# hub-carrier-p4.net
KiCad netlist of a schematic drawn in EAGLE
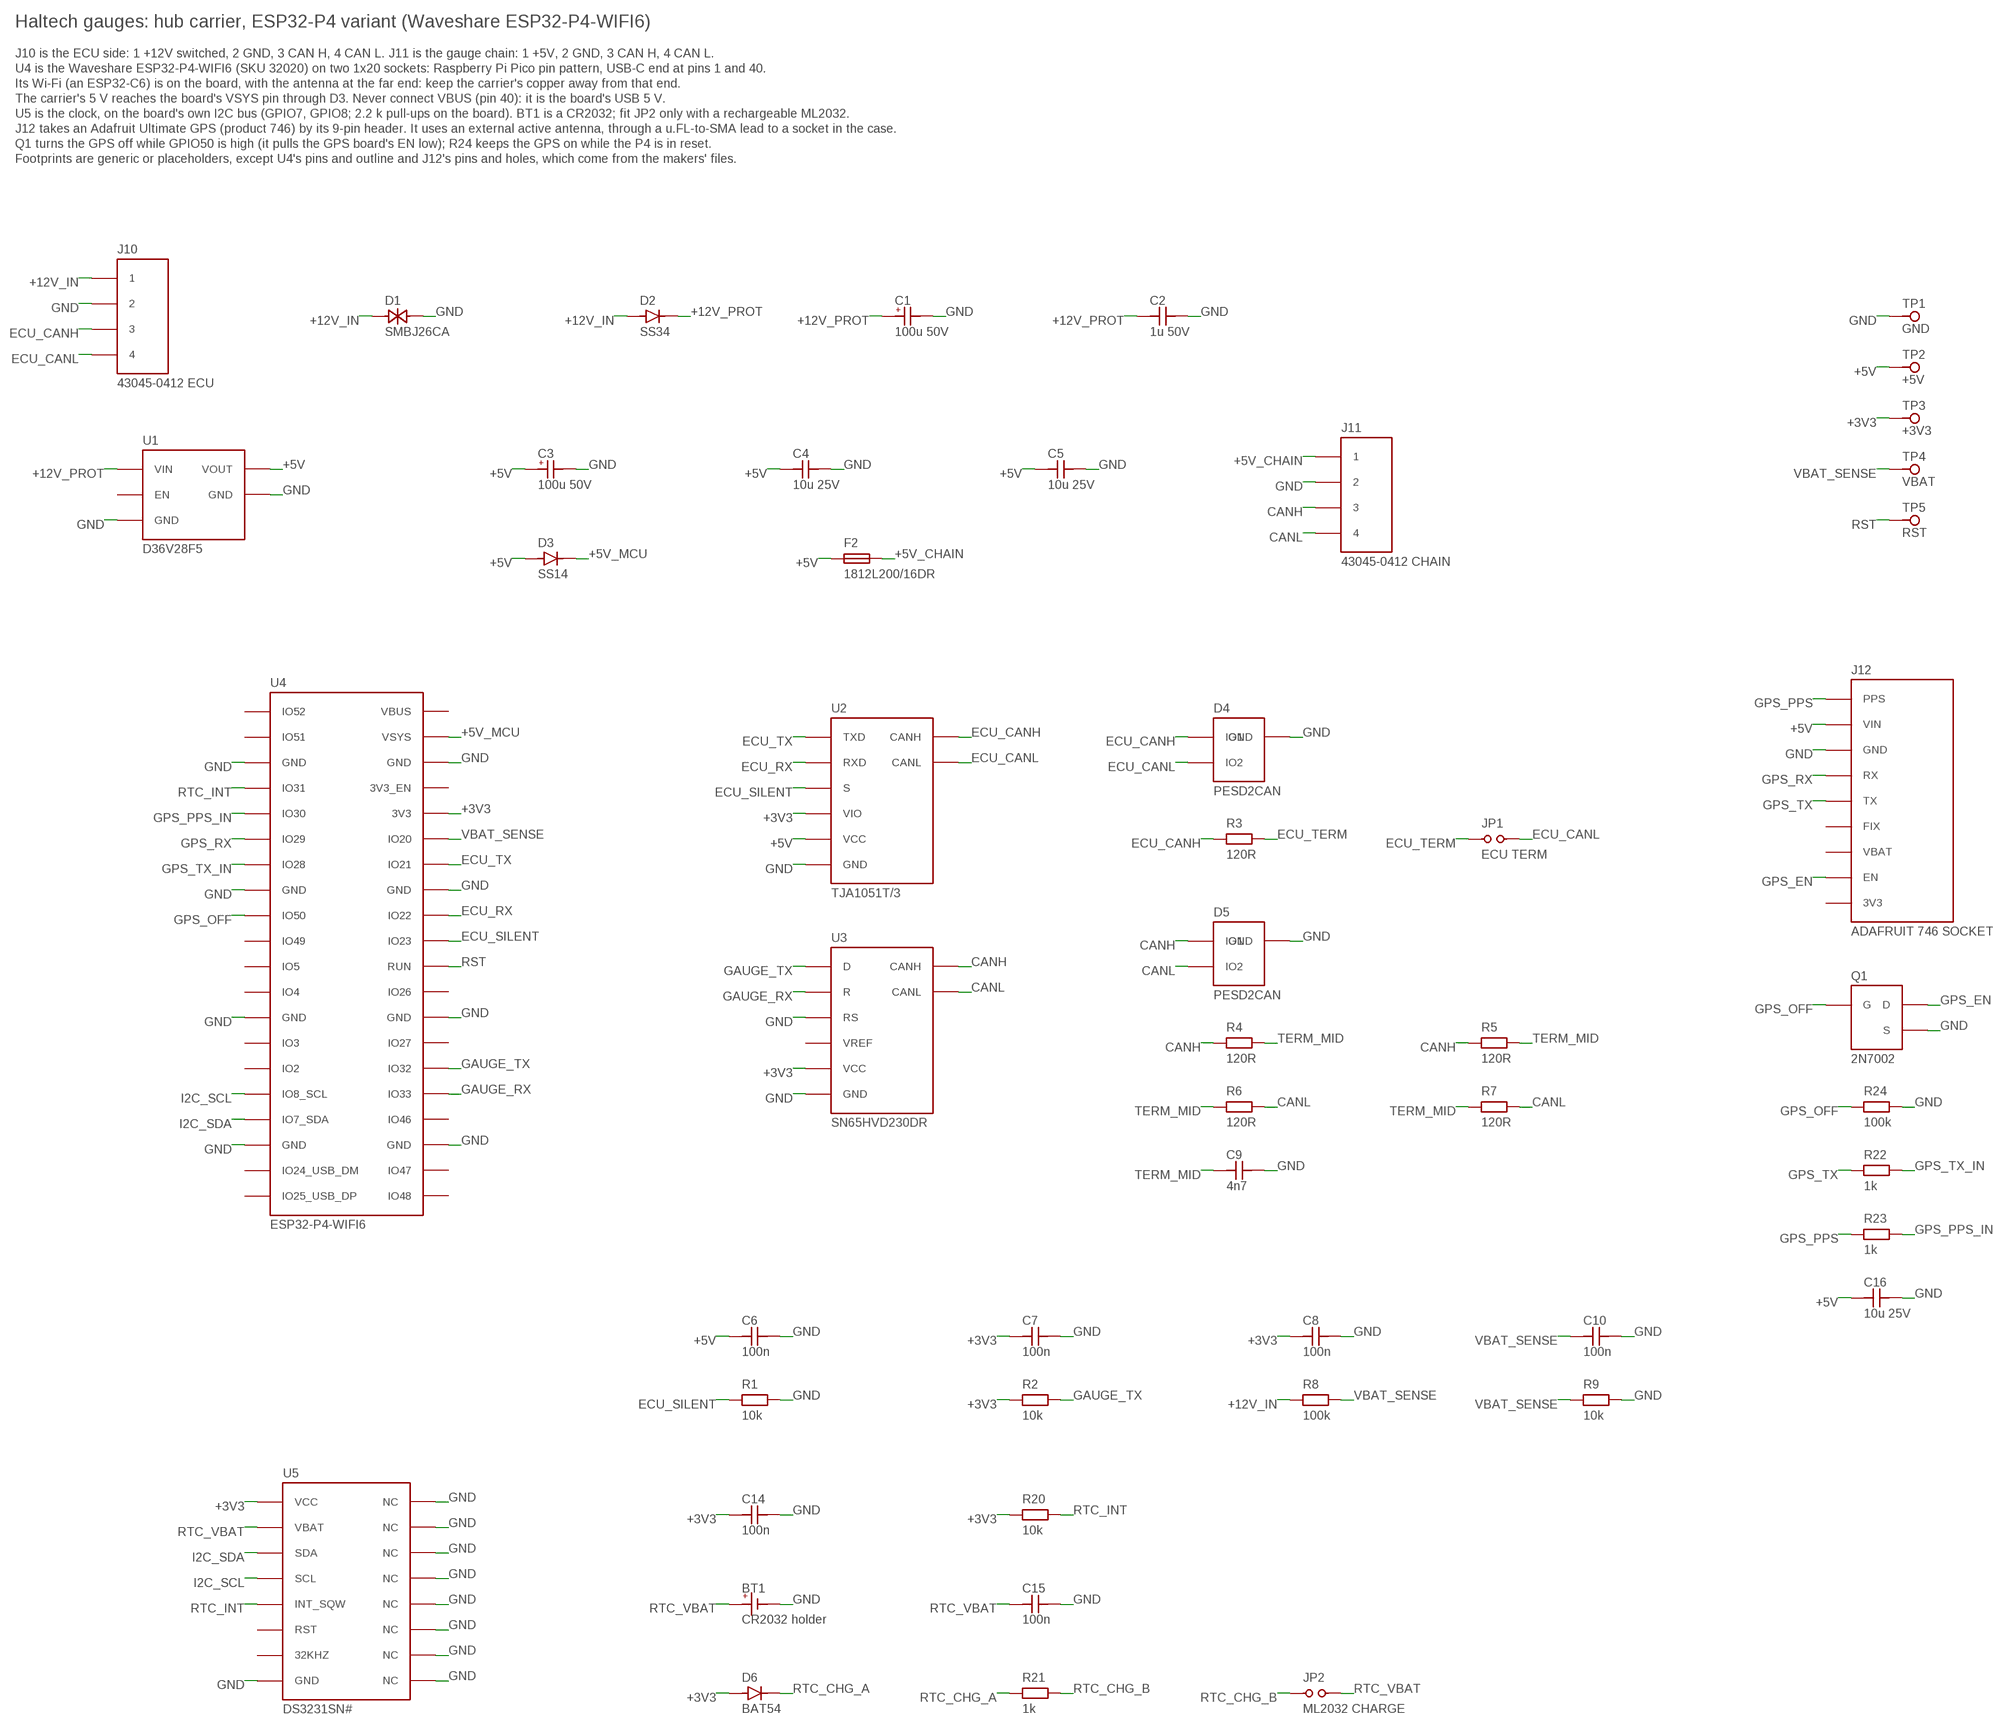
[diagram p0: schematic, sheet 1]

(export (version "E")
  (design (tool "Eeschema 10.0.6"))
  (components
    (comp (ref "BT1")
      (value "CR2032 holder")
      (footprint "eagle-import:CR2032-HOLDER-PLACEHOLDER")
      (libsource (lib "eagle-import") (part "BATTERY-2032"))
    )
    (comp (ref "C1")
      (value "100u 50V")
      (footprint "eagle-import:CAP-SMD-8X10")
      (fields (field (name "LCSC") "C116241"))
      (libsource (lib "eagle-import") (part "CPOL-8X10"))
    )
    (comp (ref "C2")
      (value "1u 50V")
      (footprint "eagle-import:0805")
      (fields (field (name "LCSC") "C28323"))
      (libsource (lib "eagle-import") (part "C0805"))
    )
    (comp (ref "C3")
      (value "100u 50V")
      (footprint "eagle-import:CAP-SMD-8X10")
      (fields (field (name "LCSC") "C116241"))
      (libsource (lib "eagle-import") (part "CPOL-8X10"))
    )
    (comp (ref "C4")
      (value "10u 25V")
      (footprint "eagle-import:0805")
      (fields (field (name "LCSC") "C15850"))
      (libsource (lib "eagle-import") (part "C0805"))
    )
    (comp (ref "C5")
      (value "10u 25V")
      (footprint "eagle-import:0805")
      (fields (field (name "LCSC") "C15850"))
      (libsource (lib "eagle-import") (part "C0805"))
    )
    (comp (ref "C6")
      (value "100n")
      (footprint "eagle-import:0805")
      (fields (field (name "LCSC") "C49678"))
      (libsource (lib "eagle-import") (part "C0805"))
    )
    (comp (ref "C7")
      (value "100n")
      (footprint "eagle-import:0805")
      (fields (field (name "LCSC") "C49678"))
      (libsource (lib "eagle-import") (part "C0805"))
    )
    (comp (ref "C8")
      (value "100n")
      (footprint "eagle-import:0805")
      (fields (field (name "LCSC") "C49678"))
      (libsource (lib "eagle-import") (part "C0805"))
    )
    (comp (ref "C9")
      (value "4n7")
      (footprint "eagle-import:0805")
      (fields (field (name "LCSC") "C1744"))
      (libsource (lib "eagle-import") (part "C0805"))
    )
    (comp (ref "C10")
      (value "100n")
      (footprint "eagle-import:0805")
      (fields (field (name "LCSC") "C49678"))
      (libsource (lib "eagle-import") (part "C0805"))
    )
    (comp (ref "C14")
      (value "100n")
      (footprint "eagle-import:0805")
      (fields (field (name "LCSC") "C49678"))
      (libsource (lib "eagle-import") (part "C0805"))
    )
    (comp (ref "C15")
      (value "100n")
      (footprint "eagle-import:0805")
      (fields (field (name "LCSC") "C49678"))
      (libsource (lib "eagle-import") (part "C0805"))
    )
    (comp (ref "C16")
      (value "10u 25V")
      (footprint "eagle-import:0805")
      (fields (field (name "LCSC") "C15850"))
      (libsource (lib "eagle-import") (part "C0805"))
    )
    (comp (ref "D1")
      (value "SMBJ26CA")
      (footprint "eagle-import:SMB")
      (fields (field (name "LCSC") "C515606"))
      (libsource (lib "eagle-import") (part "TVS-SMB"))
    )
    (comp (ref "D2")
      (value "SS34")
      (footprint "eagle-import:SMA")
      (fields (field (name "LCSC") "C8678"))
      (libsource (lib "eagle-import") (part "SCHOTTKY-SMA"))
    )
    (comp (ref "D3")
      (value "SS14")
      (footprint "eagle-import:SMA")
      (fields (field (name "LCSC") "C2480"))
      (libsource (lib "eagle-import") (part "SCHOTTKY-SMA"))
    )
    (comp (ref "D4")
      (value "PESD2CAN")
      (footprint "eagle-import:SOT23")
      (fields (field (name "LCSC") "C75176"))
      (libsource (lib "eagle-import") (part "PESD2CAN"))
    )
    (comp (ref "D5")
      (value "PESD2CAN")
      (footprint "eagle-import:SOT23")
      (fields (field (name "LCSC") "C75176"))
      (libsource (lib "eagle-import") (part "PESD2CAN"))
    )
    (comp (ref "D6")
      (value "BAT54")
      (footprint "eagle-import:SOT23")
      (fields (field (name "LCSC") "C8590"))
      (libsource (lib "eagle-import") (part "BAT54"))
    )
    (comp (ref "F2")
      (value "1812L200/16DR")
      (footprint "eagle-import:1812")
      (fields (field (name "LCSC") "C439873"))
      (libsource (lib "eagle-import") (part "POLYFUSE-1812"))
    )
    (comp (ref "J10")
      (value "43045-0412 ECU")
      (footprint "eagle-import:MOLEX-43045-0412")
      (libsource (lib "eagle-import") (part "MICROFIT-2X2"))
    )
    (comp (ref "J11")
      (value "43045-0412 CHAIN")
      (footprint "eagle-import:MOLEX-43045-0412")
      (libsource (lib "eagle-import") (part "MICROFIT-2X2"))
    )
    (comp (ref "J12")
      (value "ADAFRUIT 746 SOCKET")
      (footprint "eagle-import:ADAFRUIT-ULTIMATE-GPS")
      (libsource (lib "eagle-import") (part "ADAFRUIT-ULTIMATE-GPS"))
    )
    (comp (ref "JP1")
      (value "ECU TERM")
      (footprint "eagle-import:HDR-1X2")
      (libsource (lib "eagle-import") (part "JUMPER-2"))
    )
    (comp (ref "JP2")
      (value "ML2032 CHARGE")
      (footprint "eagle-import:HDR-1X2")
      (libsource (lib "eagle-import") (part "JUMPER-2"))
    )
    (comp (ref "Q1")
      (value "2N7002")
      (footprint "eagle-import:SOT23")
      (fields (field (name "LCSC") "C8545"))
      (libsource (lib "eagle-import") (part "2N7002"))
    )
    (comp (ref "R1")
      (value "10k")
      (footprint "eagle-import:0805")
      (fields (field (name "LCSC") "C17414"))
      (libsource (lib "eagle-import") (part "R0805"))
    )
    (comp (ref "R2")
      (value "10k")
      (footprint "eagle-import:0805")
      (fields (field (name "LCSC") "C17414"))
      (libsource (lib "eagle-import") (part "R0805"))
    )
    (comp (ref "R3")
      (value "120R")
      (footprint "eagle-import:1206")
      (fields (field (name "LCSC") "C17909"))
      (libsource (lib "eagle-import") (part "R1206"))
    )
    (comp (ref "R4")
      (value "120R")
      (footprint "eagle-import:1206")
      (fields (field (name "LCSC") "C17909"))
      (libsource (lib "eagle-import") (part "R1206"))
    )
    (comp (ref "R5")
      (value "120R")
      (footprint "eagle-import:1206")
      (fields (field (name "LCSC") "C17909"))
      (libsource (lib "eagle-import") (part "R1206"))
    )
    (comp (ref "R6")
      (value "120R")
      (footprint "eagle-import:1206")
      (fields (field (name "LCSC") "C17909"))
      (libsource (lib "eagle-import") (part "R1206"))
    )
    (comp (ref "R7")
      (value "120R")
      (footprint "eagle-import:1206")
      (fields (field (name "LCSC") "C17909"))
      (libsource (lib "eagle-import") (part "R1206"))
    )
    (comp (ref "R8")
      (value "100k")
      (footprint "eagle-import:0805")
      (fields (field (name "LCSC") "C149504"))
      (libsource (lib "eagle-import") (part "R0805"))
    )
    (comp (ref "R9")
      (value "10k")
      (footprint "eagle-import:0805")
      (fields (field (name "LCSC") "C17414"))
      (libsource (lib "eagle-import") (part "R0805"))
    )
    (comp (ref "R20")
      (value "10k")
      (footprint "eagle-import:0805")
      (fields (field (name "LCSC") "C17414"))
      (libsource (lib "eagle-import") (part "R0805"))
    )
    (comp (ref "R21")
      (value "1k")
      (footprint "eagle-import:0805")
      (fields (field (name "LCSC") "C17513"))
      (libsource (lib "eagle-import") (part "R0805"))
    )
    (comp (ref "R22")
      (value "1k")
      (footprint "eagle-import:0805")
      (fields (field (name "LCSC") "C17513"))
      (libsource (lib "eagle-import") (part "R0805"))
    )
    (comp (ref "R23")
      (value "1k")
      (footprint "eagle-import:0805")
      (fields (field (name "LCSC") "C17513"))
      (libsource (lib "eagle-import") (part "R0805"))
    )
    (comp (ref "R24")
      (value "100k")
      (footprint "eagle-import:0805")
      (fields (field (name "LCSC") "C149504"))
      (libsource (lib "eagle-import") (part "R0805"))
    )
    (comp (ref "TP1")
      (value "GND")
      (footprint "eagle-import:TESTPAD")
      (libsource (lib "eagle-import") (part "TESTPOINT"))
    )
    (comp (ref "TP2")
      (value "+5V")
      (footprint "eagle-import:TESTPAD")
      (libsource (lib "eagle-import") (part "TESTPOINT"))
    )
    (comp (ref "TP3")
      (value "+3V3")
      (footprint "eagle-import:TESTPAD")
      (libsource (lib "eagle-import") (part "TESTPOINT"))
    )
    (comp (ref "TP4")
      (value "VBAT")
      (footprint "eagle-import:TESTPAD")
      (libsource (lib "eagle-import") (part "TESTPOINT"))
    )
    (comp (ref "TP5")
      (value "RST")
      (footprint "eagle-import:TESTPAD")
      (libsource (lib "eagle-import") (part "TESTPOINT"))
    )
    (comp (ref "U1")
      (value "D36V28F5")
      (footprint "eagle-import:POLOLU-D36V28F-PLACEHOLDER")
      (libsource (lib "eagle-import") (part "POLOLU-D36V28F5"))
    )
    (comp (ref "U2")
      (value "TJA1051T/3")
      (footprint "eagle-import:SOIC8")
      (fields (field (name "LCSC") "C38695"))
      (libsource (lib "eagle-import") (part "TJA1051T-3"))
    )
    (comp (ref "U3")
      (value "SN65HVD230DR")
      (footprint "eagle-import:SOIC8")
      (fields (field (name "LCSC") "C12084"))
      (libsource (lib "eagle-import") (part "SN65HVD230"))
    )
    (comp (ref "U4")
      (value "ESP32-P4-WIFI6")
      (footprint "eagle-import:WAVESHARE-ESP32-P4-WIFI6")
      (libsource (lib "eagle-import") (part "WAVESHARE-ESP32-P4-WIFI6"))
    )
    (comp (ref "U5")
      (value "DS3231SN#")
      (footprint "eagle-import:SOIC16W")
      (fields (field (name "LCSC") "C9866"))
      (libsource (lib "eagle-import") (part "DS3231SN"))
    )
  )
  (nets
    (net (code "1") (name "/+3V3") (class "Default")
      (node (ref "C14") (pin "1") (pinfunction "1_1") (pintype "passive"))
      (node (ref "C7") (pin "1") (pinfunction "1_1") (pintype "passive"))
      (node (ref "C8") (pin "1") (pinfunction "1_1") (pintype "passive"))
      (node (ref "D6") (pin "1") (pinfunction "A_1") (pintype "passive"))
      (node (ref "R2") (pin "1") (pinfunction "1_1") (pintype "passive"))
      (node (ref "R20") (pin "1") (pinfunction "1_1") (pintype "passive"))
      (node (ref "TP3") (pin "1") (pinfunction "TP_1") (pintype "passive"))
      (node (ref "U2") (pin "5") (pinfunction "VIO_5") (pintype "passive"))
      (node (ref "U3") (pin "3") (pinfunction "VCC_3") (pintype "passive"))
      (node (ref "U4") (pin "36") (pinfunction "3V3_36") (pintype "passive"))
      (node (ref "U5") (pin "2") (pinfunction "VCC_2") (pintype "passive"))
    )
    (net (code "2") (name "/+5V") (class "Default")
      (node (ref "C16") (pin "1") (pinfunction "1_1") (pintype "passive"))
      (node (ref "C3") (pin "1") (pinfunction "+_1") (pintype "passive"))
      (node (ref "C4") (pin "1") (pinfunction "1_1") (pintype "passive"))
      (node (ref "C5") (pin "1") (pinfunction "1_1") (pintype "passive"))
      (node (ref "C6") (pin "1") (pinfunction "1_1") (pintype "passive"))
      (node (ref "D3") (pin "2") (pinfunction "A_2") (pintype "passive"))
      (node (ref "F2") (pin "1") (pinfunction "1_1") (pintype "passive"))
      (node (ref "J12") (pin "2") (pinfunction "VIN_2") (pintype "passive"))
      (node (ref "TP2") (pin "1") (pinfunction "TP_1") (pintype "passive"))
      (node (ref "U1") (pin "VOUT") (pinfunction "VOUT_VOUT") (pintype "passive"))
      (node (ref "U2") (pin "3") (pinfunction "VCC_3") (pintype "passive"))
    )
    (net (code "3") (name "/+5V_CHAIN") (class "Default")
      (node (ref "F2") (pin "2") (pinfunction "2_2") (pintype "passive"))
      (node (ref "J11") (pin "1") (pinfunction "1_1") (pintype "passive"))
    )
    (net (code "4") (name "/+5V_MCU") (class "Default")
      (node (ref "D3") (pin "1") (pinfunction "K_1") (pintype "passive"))
      (node (ref "U4") (pin "39") (pinfunction "VSYS_39") (pintype "passive"))
    )
    (net (code "5") (name "/+12V_IN") (class "Default")
      (node (ref "D1") (pin "1") (pinfunction "1_1") (pintype "passive"))
      (node (ref "D2") (pin "2") (pinfunction "A_2") (pintype "passive"))
      (node (ref "J10") (pin "1") (pinfunction "1_1") (pintype "passive"))
      (node (ref "R8") (pin "1") (pinfunction "1_1") (pintype "passive"))
    )
    (net (code "6") (name "/+12V_PROT") (class "Default")
      (node (ref "C1") (pin "1") (pinfunction "+_1") (pintype "passive"))
      (node (ref "C2") (pin "1") (pinfunction "1_1") (pintype "passive"))
      (node (ref "D2") (pin "1") (pinfunction "K_1") (pintype "passive"))
      (node (ref "U1") (pin "VIN") (pinfunction "VIN_VIN") (pintype "passive"))
    )
    (net (code "7") (name "/CANH") (class "Default")
      (node (ref "D5") (pin "1") (pinfunction "IO1_1") (pintype "passive"))
      (node (ref "J11") (pin "3") (pinfunction "3_3") (pintype "passive"))
      (node (ref "R4") (pin "1") (pinfunction "1_1") (pintype "passive"))
      (node (ref "R5") (pin "1") (pinfunction "1_1") (pintype "passive"))
      (node (ref "U3") (pin "7") (pinfunction "CANH_7") (pintype "passive"))
    )
    (net (code "8") (name "/CANL") (class "Default")
      (node (ref "D5") (pin "2") (pinfunction "IO2_2") (pintype "passive"))
      (node (ref "J11") (pin "4") (pinfunction "4_4") (pintype "passive"))
      (node (ref "R6") (pin "2") (pinfunction "2_2") (pintype "passive"))
      (node (ref "R7") (pin "2") (pinfunction "2_2") (pintype "passive"))
      (node (ref "U3") (pin "6") (pinfunction "CANL_6") (pintype "passive"))
    )
    (net (code "9") (name "/ECU_CANH") (class "Default")
      (node (ref "D4") (pin "1") (pinfunction "IO1_1") (pintype "passive"))
      (node (ref "J10") (pin "3") (pinfunction "3_3") (pintype "passive"))
      (node (ref "R3") (pin "1") (pinfunction "1_1") (pintype "passive"))
      (node (ref "U2") (pin "7") (pinfunction "CANH_7") (pintype "passive"))
    )
    (net (code "10") (name "/ECU_CANL") (class "Default")
      (node (ref "D4") (pin "2") (pinfunction "IO2_2") (pintype "passive"))
      (node (ref "J10") (pin "4") (pinfunction "4_4") (pintype "passive"))
      (node (ref "JP1") (pin "2") (pinfunction "2_2") (pintype "passive"))
      (node (ref "U2") (pin "6") (pinfunction "CANL_6") (pintype "passive"))
    )
    (net (code "11") (name "/ECU_RX") (class "Default")
      (node (ref "U2") (pin "4") (pinfunction "RXD_4") (pintype "passive"))
      (node (ref "U4") (pin "32") (pinfunction "IO22_32") (pintype "passive"))
    )
    (net (code "12") (name "/ECU_SILENT") (class "Default")
      (node (ref "R1") (pin "1") (pinfunction "1_1") (pintype "passive"))
      (node (ref "U2") (pin "8") (pinfunction "S_8") (pintype "passive"))
      (node (ref "U4") (pin "31") (pinfunction "IO23_31") (pintype "passive"))
    )
    (net (code "13") (name "/ECU_TERM") (class "Default")
      (node (ref "JP1") (pin "1") (pinfunction "1_1") (pintype "passive"))
      (node (ref "R3") (pin "2") (pinfunction "2_2") (pintype "passive"))
    )
    (net (code "14") (name "/ECU_TX") (class "Default")
      (node (ref "U2") (pin "1") (pinfunction "TXD_1") (pintype "passive"))
      (node (ref "U4") (pin "34") (pinfunction "IO21_34") (pintype "passive"))
    )
    (net (code "15") (name "/GAUGE_RX") (class "Default")
      (node (ref "U3") (pin "4") (pinfunction "R_4") (pintype "passive"))
      (node (ref "U4") (pin "25") (pinfunction "IO33_25") (pintype "passive"))
    )
    (net (code "16") (name "/GAUGE_TX") (class "Default")
      (node (ref "R2") (pin "2") (pinfunction "2_2") (pintype "passive"))
      (node (ref "U3") (pin "1") (pinfunction "D_1") (pintype "passive"))
      (node (ref "U4") (pin "26") (pinfunction "IO32_26") (pintype "passive"))
    )
    (net (code "17") (name "/GND") (class "Default")
      (node (ref "BT1") (pin "NEG") (pinfunction "-_NEG") (pintype "passive"))
      (node (ref "C1") (pin "2") (pinfunction "-_2") (pintype "passive"))
      (node (ref "C10") (pin "2") (pinfunction "2_2") (pintype "passive"))
      (node (ref "C14") (pin "2") (pinfunction "2_2") (pintype "passive"))
      (node (ref "C15") (pin "2") (pinfunction "2_2") (pintype "passive"))
      (node (ref "C16") (pin "2") (pinfunction "2_2") (pintype "passive"))
      (node (ref "C2") (pin "2") (pinfunction "2_2") (pintype "passive"))
      (node (ref "C3") (pin "2") (pinfunction "-_2") (pintype "passive"))
      (node (ref "C4") (pin "2") (pinfunction "2_2") (pintype "passive"))
      (node (ref "C5") (pin "2") (pinfunction "2_2") (pintype "passive"))
      (node (ref "C6") (pin "2") (pinfunction "2_2") (pintype "passive"))
      (node (ref "C7") (pin "2") (pinfunction "2_2") (pintype "passive"))
      (node (ref "C8") (pin "2") (pinfunction "2_2") (pintype "passive"))
      (node (ref "C9") (pin "2") (pinfunction "2_2") (pintype "passive"))
      (node (ref "D1") (pin "2") (pinfunction "2_2") (pintype "passive"))
      (node (ref "D4") (pin "3") (pinfunction "GND_3") (pintype "passive"))
      (node (ref "D5") (pin "3") (pinfunction "GND_3") (pintype "passive"))
      (node (ref "J10") (pin "2") (pinfunction "2_2") (pintype "passive"))
      (node (ref "J11") (pin "2") (pinfunction "2_2") (pintype "passive"))
      (node (ref "J12") (pin "3") (pinfunction "GND_3") (pintype "passive"))
      (node (ref "Q1") (pin "2") (pinfunction "S_2") (pintype "passive"))
      (node (ref "R1") (pin "2") (pinfunction "2_2") (pintype "passive"))
      (node (ref "R24") (pin "2") (pinfunction "2_2") (pintype "passive"))
      (node (ref "R9") (pin "2") (pinfunction "2_2") (pintype "passive"))
      (node (ref "TP1") (pin "1") (pinfunction "TP_1") (pintype "passive"))
      (node (ref "U1") (pin "GND1") (pinfunction "GND_GND1") (pintype "passive"))
      (node (ref "U1") (pin "GND2") (pinfunction "GND_GND2") (pintype "passive"))
      (node (ref "U2") (pin "2") (pinfunction "GND_2") (pintype "passive"))
      (node (ref "U3") (pin "2") (pinfunction "GND_2") (pintype "passive"))
      (node (ref "U3") (pin "8") (pinfunction "RS_8") (pintype "passive"))
      (node (ref "U4") (pin "13") (pinfunction "GND_13") (pintype "passive"))
      (node (ref "U4") (pin "18") (pinfunction "GND_18") (pintype "passive"))
      (node (ref "U4") (pin "23") (pinfunction "GND_23") (pintype "passive"))
      (node (ref "U4") (pin "28") (pinfunction "GND_28") (pintype "passive"))
      (node (ref "U4") (pin "3") (pinfunction "GND_3") (pintype "passive"))
      (node (ref "U4") (pin "33") (pinfunction "GND_33") (pintype "passive"))
      (node (ref "U4") (pin "38") (pinfunction "GND_38") (pintype "passive"))
      (node (ref "U4") (pin "8") (pinfunction "GND_8") (pintype "passive"))
      (node (ref "U5") (pin "10") (pinfunction "NC_10") (pintype "passive"))
      (node (ref "U5") (pin "11") (pinfunction "NC_11") (pintype "passive"))
      (node (ref "U5") (pin "12") (pinfunction "NC_12") (pintype "passive"))
      (node (ref "U5") (pin "13") (pinfunction "GND_13") (pintype "passive"))
      (node (ref "U5") (pin "5") (pinfunction "NC_5") (pintype "passive"))
      (node (ref "U5") (pin "6") (pinfunction "NC_6") (pintype "passive"))
      (node (ref "U5") (pin "7") (pinfunction "NC_7") (pintype "passive"))
      (node (ref "U5") (pin "8") (pinfunction "NC_8") (pintype "passive"))
      (node (ref "U5") (pin "9") (pinfunction "NC_9") (pintype "passive"))
    )
    (net (code "18") (name "/GPS_EN") (class "Default")
      (node (ref "J12") (pin "8") (pinfunction "EN_8") (pintype "passive"))
      (node (ref "Q1") (pin "3") (pinfunction "D_3") (pintype "passive"))
    )
    (net (code "19") (name "/GPS_OFF") (class "Default")
      (node (ref "Q1") (pin "1") (pinfunction "G_1") (pintype "passive"))
      (node (ref "R24") (pin "1") (pinfunction "1_1") (pintype "passive"))
      (node (ref "U4") (pin "9") (pinfunction "IO50_9") (pintype "passive"))
    )
    (net (code "20") (name "/GPS_PPS") (class "Default")
      (node (ref "J12") (pin "1") (pinfunction "PPS_1") (pintype "passive"))
      (node (ref "R23") (pin "1") (pinfunction "1_1") (pintype "passive"))
    )
    (net (code "21") (name "/GPS_PPS_IN") (class "Default")
      (node (ref "R23") (pin "2") (pinfunction "2_2") (pintype "passive"))
      (node (ref "U4") (pin "5") (pinfunction "IO30_5") (pintype "passive"))
    )
    (net (code "22") (name "/GPS_RX") (class "Default")
      (node (ref "J12") (pin "4") (pinfunction "RX_4") (pintype "passive"))
      (node (ref "U4") (pin "6") (pinfunction "IO29_6") (pintype "passive"))
    )
    (net (code "23") (name "/GPS_TX") (class "Default")
      (node (ref "J12") (pin "5") (pinfunction "TX_5") (pintype "passive"))
      (node (ref "R22") (pin "1") (pinfunction "1_1") (pintype "passive"))
    )
    (net (code "24") (name "/GPS_TX_IN") (class "Default")
      (node (ref "R22") (pin "2") (pinfunction "2_2") (pintype "passive"))
      (node (ref "U4") (pin "7") (pinfunction "IO28_7") (pintype "passive"))
    )
    (net (code "25") (name "/I2C_SCL") (class "Default")
      (node (ref "U4") (pin "16") (pinfunction "IO8_SCL_16") (pintype "passive"))
      (node (ref "U5") (pin "16") (pinfunction "SCL_16") (pintype "passive"))
    )
    (net (code "26") (name "/I2C_SDA") (class "Default")
      (node (ref "U4") (pin "17") (pinfunction "IO7_SDA_17") (pintype "passive"))
      (node (ref "U5") (pin "15") (pinfunction "SDA_15") (pintype "passive"))
    )
    (net (code "27") (name "/RST") (class "Default")
      (node (ref "TP5") (pin "1") (pinfunction "TP_1") (pintype "passive"))
      (node (ref "U4") (pin "30") (pinfunction "RUN_30") (pintype "passive"))
    )
    (net (code "28") (name "/RTC_CHG_A") (class "Default")
      (node (ref "D6") (pin "3") (pinfunction "K_3") (pintype "passive"))
      (node (ref "R21") (pin "1") (pinfunction "1_1") (pintype "passive"))
    )
    (net (code "29") (name "/RTC_CHG_B") (class "Default")
      (node (ref "JP2") (pin "1") (pinfunction "1_1") (pintype "passive"))
      (node (ref "R21") (pin "2") (pinfunction "2_2") (pintype "passive"))
    )
    (net (code "30") (name "/RTC_INT") (class "Default")
      (node (ref "R20") (pin "2") (pinfunction "2_2") (pintype "passive"))
      (node (ref "U4") (pin "4") (pinfunction "IO31_4") (pintype "passive"))
      (node (ref "U5") (pin "3") (pinfunction "INT_SQW_3") (pintype "passive"))
    )
    (net (code "31") (name "/RTC_VBAT") (class "Default")
      (node (ref "BT1") (pin "POS") (pinfunction "+_POS") (pintype "passive"))
      (node (ref "C15") (pin "1") (pinfunction "1_1") (pintype "passive"))
      (node (ref "JP2") (pin "2") (pinfunction "2_2") (pintype "passive"))
      (node (ref "U5") (pin "14") (pinfunction "VBAT_14") (pintype "passive"))
    )
    (net (code "32") (name "/TERM_MID") (class "Default")
      (node (ref "C9") (pin "1") (pinfunction "1_1") (pintype "passive"))
      (node (ref "R4") (pin "2") (pinfunction "2_2") (pintype "passive"))
      (node (ref "R5") (pin "2") (pinfunction "2_2") (pintype "passive"))
      (node (ref "R6") (pin "1") (pinfunction "1_1") (pintype "passive"))
      (node (ref "R7") (pin "1") (pinfunction "1_1") (pintype "passive"))
    )
    (net (code "33") (name "/VBAT_SENSE") (class "Default")
      (node (ref "C10") (pin "1") (pinfunction "1_1") (pintype "passive"))
      (node (ref "R8") (pin "2") (pinfunction "2_2") (pintype "passive"))
      (node (ref "R9") (pin "1") (pinfunction "1_1") (pintype "passive"))
      (node (ref "TP4") (pin "1") (pinfunction "TP_1") (pintype "passive"))
      (node (ref "U4") (pin "35") (pinfunction "IO20_35") (pintype "passive"))
    )
    (net (code "34") (name "unconnected-(J12-3V3-Pad9)") (class "Default")
      (node (ref "J12") (pin "9") (pinfunction "3V3_9") (pintype "passive"))
    )
    (net (code "35") (name "unconnected-(J12-FIX-Pad6)") (class "Default")
      (node (ref "J12") (pin "6") (pinfunction "FIX_6") (pintype "passive"))
    )
    (net (code "36") (name "unconnected-(J12-VBAT-Pad7)") (class "Default")
      (node (ref "J12") (pin "7") (pinfunction "VBAT_7") (pintype "passive"))
    )
    (net (code "37") (name "unconnected-(U1-PadEN)") (class "Default")
      (node (ref "U1") (pin "EN") (pinfunction "EN_EN") (pintype "passive"))
    )
    (net (code "38") (name "unconnected-(U3-VREF-Pad5)") (class "Default")
      (node (ref "U3") (pin "5") (pinfunction "VREF_5") (pintype "passive"))
    )
    (net (code "39") (name "unconnected-(U4-3V3_EN-Pad37)") (class "Default")
      (node (ref "U4") (pin "37") (pinfunction "3V3_EN_37") (pintype "passive"))
    )
    (net (code "40") (name "unconnected-(U4-IO2-Pad15)") (class "Default")
      (node (ref "U4") (pin "15") (pinfunction "IO2_15") (pintype "passive"))
    )
    (net (code "41") (name "unconnected-(U4-IO3-Pad14)") (class "Default")
      (node (ref "U4") (pin "14") (pinfunction "IO3_14") (pintype "passive"))
    )
    (net (code "42") (name "unconnected-(U4-IO4-Pad12)") (class "Default")
      (node (ref "U4") (pin "12") (pinfunction "IO4_12") (pintype "passive"))
    )
    (net (code "43") (name "unconnected-(U4-IO5-Pad11)") (class "Default")
      (node (ref "U4") (pin "11") (pinfunction "IO5_11") (pintype "passive"))
    )
    (net (code "44") (name "unconnected-(U4-IO24_USB_DM-Pad19)") (class "Default")
      (node (ref "U4") (pin "19") (pinfunction "IO24_USB_DM_19") (pintype "passive"))
    )
    (net (code "45") (name "unconnected-(U4-IO25_USB_DP-Pad20)") (class "Default")
      (node (ref "U4") (pin "20") (pinfunction "IO25_USB_DP_20") (pintype "passive"))
    )
    (net (code "46") (name "unconnected-(U4-IO26-Pad29)") (class "Default")
      (node (ref "U4") (pin "29") (pinfunction "IO26_29") (pintype "passive"))
    )
    (net (code "47") (name "unconnected-(U4-IO27-Pad27)") (class "Default")
      (node (ref "U4") (pin "27") (pinfunction "IO27_27") (pintype "passive"))
    )
    (net (code "48") (name "unconnected-(U4-IO46-Pad24)") (class "Default")
      (node (ref "U4") (pin "24") (pinfunction "IO46_24") (pintype "passive"))
    )
    (net (code "49") (name "unconnected-(U4-IO47-Pad22)") (class "Default")
      (node (ref "U4") (pin "22") (pinfunction "IO47_22") (pintype "passive"))
    )
    (net (code "50") (name "unconnected-(U4-IO48-Pad21)") (class "Default")
      (node (ref "U4") (pin "21") (pinfunction "IO48_21") (pintype "passive"))
    )
    (net (code "51") (name "unconnected-(U4-IO49-Pad10)") (class "Default")
      (node (ref "U4") (pin "10") (pinfunction "IO49_10") (pintype "passive"))
    )
    (net (code "52") (name "unconnected-(U4-IO51-Pad2)") (class "Default")
      (node (ref "U4") (pin "2") (pinfunction "IO51_2") (pintype "passive"))
    )
    (net (code "53") (name "unconnected-(U4-IO52-Pad1)") (class "Default")
      (node (ref "U4") (pin "1") (pinfunction "IO52_1") (pintype "passive"))
    )
    (net (code "54") (name "unconnected-(U4-VBUS-Pad40)") (class "Default")
      (node (ref "U4") (pin "40") (pinfunction "VBUS_40") (pintype "passive"))
    )
    (net (code "55") (name "unconnected-(U5-32KHZ-Pad1)") (class "Default")
      (node (ref "U5") (pin "1") (pinfunction "32KHZ_1") (pintype "passive"))
    )
    (net (code "56") (name "unconnected-(U5-RST-Pad4)") (class "Default")
      (node (ref "U5") (pin "4") (pinfunction "RST_4") (pintype "passive"))
    )
  )
)
